# working.net
KiCad netlist of a schematic drawn in EAGLE
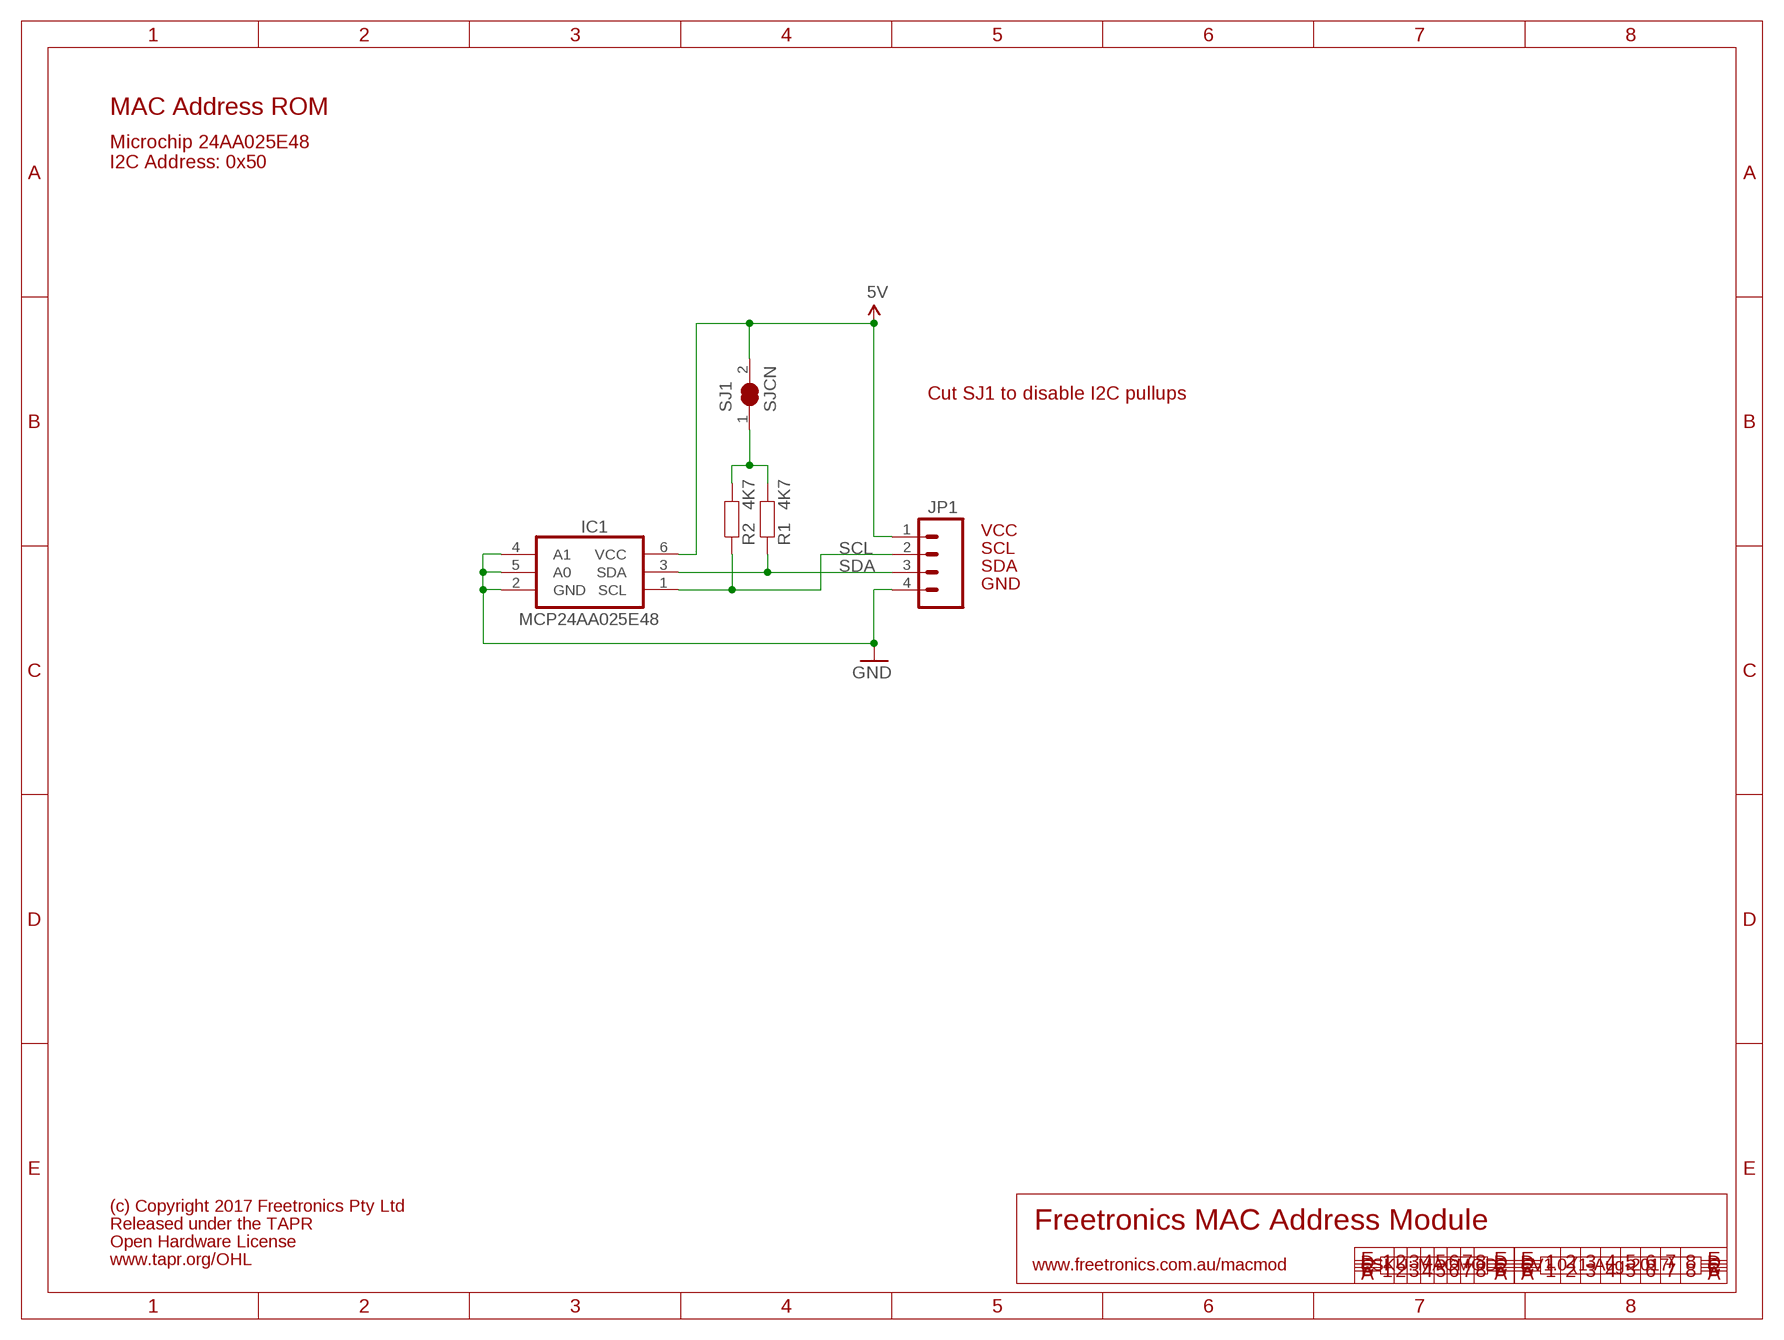
[diagram p0: schematic, sheet 1]

(export (version "E")
  (design (tool "Eeschema 10.0.6"))
  (components
    (comp (ref "IC1")
      (value "MCP24AA025E48")
      (footprint "eagle-import:SOT23-6")
      (libsource (lib "eagle-import") (part "MCP24AA025E48"))
    )
    (comp (ref "JP1")
      (value "M04PTH")
      (footprint "eagle-import:1X04")
      (libsource (lib "eagle-import") (part "M04PTH"))
    )
    (comp (ref "R1")
      (value "4K7")
      (footprint "eagle-import:0603")
      (libsource (lib "eagle-import") (part "RESISTOR0603"))
    )
    (comp (ref "R2")
      (value "4K7")
      (footprint "eagle-import:0603")
      (libsource (lib "eagle-import") (part "RESISTOR0603"))
    )
    (comp (ref "SJ1")
      (value "SJCN")
      (footprint "eagle-import:SJC")
      (libsource (lib "eagle-import") (part "SJCN"))
    )
  )
  (nets
    (net (code "1") (name "/SCL") (class "Default")
      (node (ref "IC1") (pin "1") (pinfunction "SCL_1") (pintype "bidirectional"))
      (node (ref "JP1") (pin "2") (pinfunction "2_2") (pintype "passive"))
      (node (ref "R2") (pin "1") (pinfunction "1_1") (pintype "passive"))
    )
    (net (code "2") (name "/SDA") (class "Default")
      (node (ref "IC1") (pin "3") (pinfunction "SDA_3") (pintype "bidirectional"))
      (node (ref "JP1") (pin "3") (pinfunction "3_3") (pintype "passive"))
      (node (ref "R1") (pin "1") (pinfunction "1_1") (pintype "passive"))
    )
    (net (code "3") (name "5V") (class "Default")
      (node (ref "IC1") (pin "6") (pinfunction "VCC_6") (pintype "power_in"))
      (node (ref "JP1") (pin "1") (pinfunction "1_1") (pintype "passive"))
      (node (ref "SJ1") (pin "2") (pinfunction "2_2") (pintype "passive"))
    )
    (net (code "4") (name "GND") (class "Default")
      (node (ref "IC1") (pin "2") (pinfunction "GND_2") (pintype "power_in"))
      (node (ref "IC1") (pin "4") (pinfunction "A1_4") (pintype "input"))
      (node (ref "IC1") (pin "5") (pinfunction "A0_5") (pintype "input"))
      (node (ref "JP1") (pin "4") (pinfunction "4_4") (pintype "passive"))
    )
    (net (code "5") (name "Net-(R1-Pad2)") (class "Default")
      (node (ref "R1") (pin "2") (pinfunction "2_2") (pintype "passive"))
      (node (ref "R2") (pin "2") (pinfunction "2_2") (pintype "passive"))
      (node (ref "SJ1") (pin "1") (pinfunction "1_1") (pintype "passive"))
    )
  )
)
